# POWER.net
KiCad netlist of a schematic drawn in Altium Designer
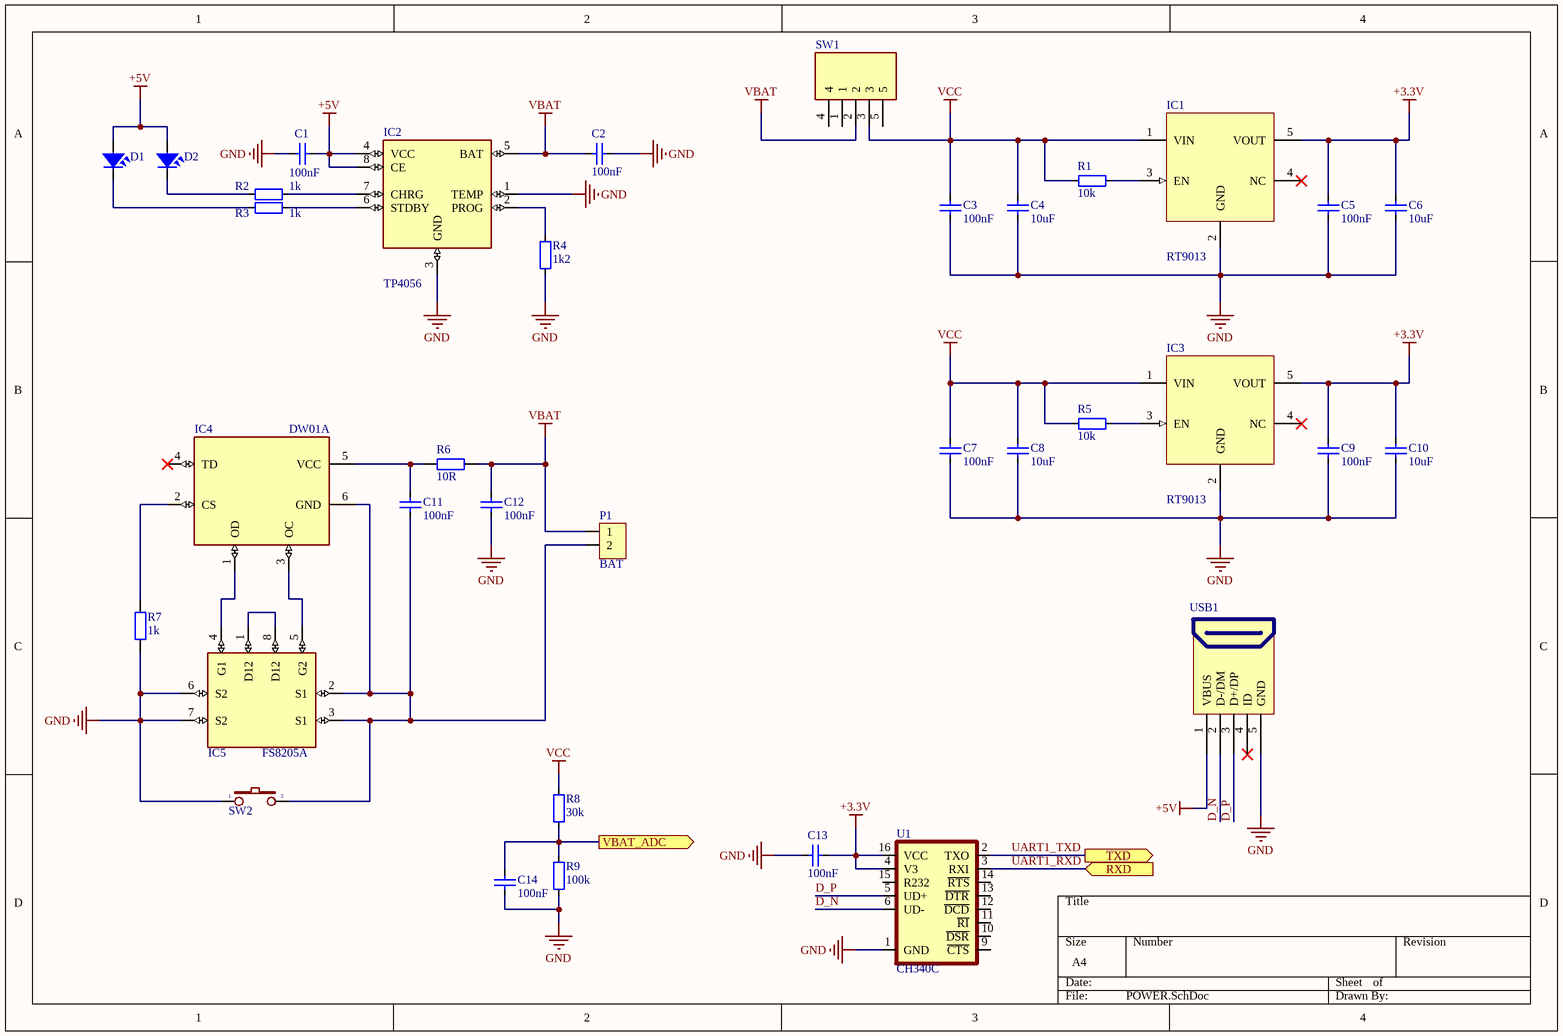
[diagram p0: POWER.SchDoc]

(export (version "E")
  (design (tool "Eeschema 10.0.6"))
  (components
    (comp (ref "C1")
      (value "100nF")
      (footprint "CAP_0603")
      (description "Capacitor")
      (fields (field (name "PUBLISHER") "Altium Limited"))
      (libsource (lib "My Library") (part "CapSMD"))
    )
    (comp (ref "C2")
      (value "100nF")
      (footprint "CAP_0603")
      (description "Capacitor")
      (fields (field (name "PUBLISHER") "Altium Limited"))
      (libsource (lib "My Library") (part "CapSMD"))
    )
    (comp (ref "C3")
      (value "100nF")
      (footprint "CAP_0603")
      (description "Capacitor")
      (fields (field (name "PUBLISHER") "Altium Limited"))
      (libsource (lib "My Library") (part "CapSMD"))
    )
    (comp (ref "C4")
      (value "10uF")
      (footprint "CAP_0603")
      (description "Capacitor")
      (fields (field (name "PUBLISHER") "Altium Limited"))
      (libsource (lib "My Library") (part "CapSMD"))
    )
    (comp (ref "C5")
      (value "100nF")
      (footprint "CAP_0603")
      (description "Capacitor")
      (fields (field (name "PUBLISHER") "Altium Limited"))
      (libsource (lib "My Library") (part "CapSMD"))
    )
    (comp (ref "C6")
      (value "10uF")
      (footprint "CAP_0603")
      (description "Capacitor")
      (fields (field (name "PUBLISHER") "Altium Limited"))
      (libsource (lib "My Library") (part "CapSMD"))
    )
    (comp (ref "C7")
      (value "100nF")
      (footprint "CAP_0603")
      (description "Capacitor")
      (fields (field (name "PUBLISHER") "Altium Limited"))
      (libsource (lib "My Library") (part "CapSMD"))
    )
    (comp (ref "C8")
      (value "10uF")
      (footprint "CAP_0603")
      (description "Capacitor")
      (fields (field (name "PUBLISHER") "Altium Limited"))
      (libsource (lib "My Library") (part "CapSMD"))
    )
    (comp (ref "C9")
      (value "100nF")
      (footprint "CAP_0603")
      (description "Capacitor")
      (fields (field (name "PUBLISHER") "Altium Limited"))
      (libsource (lib "My Library") (part "CapSMD"))
    )
    (comp (ref "C10")
      (value "10uF")
      (footprint "CAP_0603")
      (description "Capacitor")
      (fields (field (name "PUBLISHER") "Altium Limited"))
      (libsource (lib "My Library") (part "CapSMD"))
    )
    (comp (ref "C11")
      (value "100nF")
      (footprint "CAP_0603")
      (description "Capacitor")
      (fields (field (name "PUBLISHER") "Altium Limited"))
      (libsource (lib "My Library") (part "CapSMD"))
    )
    (comp (ref "C12")
      (value "100nF")
      (footprint "CAP_0603")
      (description "Capacitor")
      (fields (field (name "PUBLISHER") "Altium Limited"))
      (libsource (lib "My Library") (part "CapSMD"))
    )
    (comp (ref "C13")
      (value "100nF")
      (footprint "CAP_0603")
      (description "Capacitor")
      (fields (field (name "PUBLISHER") "Altium Limited"))
      (libsource (lib "My Library") (part "CapSMD"))
    )
    (comp (ref "C14")
      (value "100nF")
      (footprint "CAP_0603")
      (description "Capacitor")
      (fields (field (name "PUBLISHER") "Altium Limited"))
      (libsource (lib "My Library") (part "CapSMD"))
    )
    (comp (ref "D1")
      (value "BLUE")
      (footprint "LED-0603-Green")
      (description "LED Single colour Green and Red")
      (libsource (lib "My Library") (part "LED"))
    )
    (comp (ref "D2")
      (value "BLUE")
      (footprint "LED-0603-Green")
      (description "LED Single colour Green and Red")
      (libsource (lib "My Library") (part "LED"))
    )
    (comp (ref "IC1")
      (value "RT9013")
      (footprint "SOT23-5")
      (description "RT9013-33GB IC REG LINEAR 3.3V 500mA SOT23-5")
      (libsource (lib "My Library") (part "RT9013"))
    )
    (comp (ref "IC2")
      (value "TP4056")
      (footprint "TP4056")
      (description "Complete single cell Li-Ion battery with a constant current / constant voltage linear charger")
      (libsource (lib "My Library") (part "TP4056"))
    )
    (comp (ref "IC3")
      (value "RT9013")
      (footprint "SOT23-5")
      (description "RT9013-33GB IC REG LINEAR 3.3V 500mA SOT23-5")
      (libsource (lib "My Library") (part "RT9013"))
    )
    (comp (ref "IC4")
      (value "DW01A")
      (footprint "SOT23-6")
      (description "One Cell Lithium-ion/Polymer Battery Protection IC")
      (libsource (lib "My Library") (part "DW01A"))
    )
    (comp (ref "IC5") (value "FS8205A") (footprint "FS8205A") (libsource (lib "My Library") (part "FS8205A")))
    (comp (ref "P1")
      (value "BAT")
      (footprint "HEAD2P-1.25")
      (description "Header IDC, 2 x 1 Pin Vertical 2.54mm Pitch (Non-Boxed, Male)")
      (fields
        (field (name "MANUFACTURER") "Würth Elektronik eiSos GmbH")
        (field (name "PARTNO") "613002143121")
        (field (name "CREATED BY") "Karrer Zheng")
      )
      (libsource (lib "My Library") (part "Header2"))
    )
    (comp (ref "R1")
      (value "10k")
      (footprint "RES-SMD-0603")
      (description "Resistor")
      (fields
        (field (name "MANUFACTURER") "Generic Components")
        (field (name "PUBLISHER") "Altium Hobart Technology Centre")
      )
      (libsource (lib "My Library") (part "Resistor - SMD"))
    )
    (comp (ref "R2")
      (value "1k")
      (footprint "RES-SMD-0603")
      (description "Resistor")
      (fields
        (field (name "MANUFACTURER") "Generic Components")
        (field (name "PUBLISHER") "Altium Hobart Technology Centre")
      )
      (libsource (lib "My Library") (part "Resistor - SMD"))
    )
    (comp (ref "R3")
      (value "1k")
      (footprint "RES-SMD-0603")
      (description "Resistor")
      (fields
        (field (name "MANUFACTURER") "Generic Components")
        (field (name "PUBLISHER") "Altium Hobart Technology Centre")
      )
      (libsource (lib "My Library") (part "Resistor - SMD"))
    )
    (comp (ref "R4")
      (value "1k2")
      (footprint "RES-SMD-0603")
      (description "Resistor")
      (fields
        (field (name "MANUFACTURER") "Generic Components")
        (field (name "PUBLISHER") "Altium Hobart Technology Centre")
      )
      (libsource (lib "My Library") (part "Resistor - SMD"))
    )
    (comp (ref "R5")
      (value "10k")
      (footprint "RES-SMD-0603")
      (description "Resistor")
      (fields
        (field (name "MANUFACTURER") "Generic Components")
        (field (name "PUBLISHER") "Altium Hobart Technology Centre")
      )
      (libsource (lib "My Library") (part "Resistor - SMD"))
    )
    (comp (ref "R6")
      (value "10R")
      (footprint "RES-SMD-0603")
      (description "Resistor SMD")
      (fields
        (field (name "MANUFACTURER") "Generic Components")
        (field (name "PUBLISHER") "Altium Hobart Technology Centre")
      )
      (libsource (lib "") (part "Resistor - SMD_1"))
    )
    (comp (ref "R7")
      (value "1k")
      (footprint "RES-SMD-0603")
      (description "Resistor SMD")
      (fields
        (field (name "MANUFACTURER") "Generic Components")
        (field (name "PUBLISHER") "Altium Hobart Technology Centre")
      )
      (libsource (lib "") (part "Resistor - SMD_1"))
    )
    (comp (ref "R8")
      (value "30k")
      (footprint "RES-SMD-0603")
      (description "Resistor")
      (fields
        (field (name "MANUFACTURER") "Generic Components")
        (field (name "PUBLISHER") "Altium Hobart Technology Centre")
      )
      (libsource (lib "My Library") (part "Resistor - SMD"))
    )
    (comp (ref "R9")
      (value "100k")
      (footprint "RES-SMD-0603")
      (description "Resistor")
      (fields
        (field (name "MANUFACTURER") "Generic Components")
        (field (name "PUBLISHER") "Altium Hobart Technology Centre")
      )
      (libsource (lib "My Library") (part "Resistor - SMD"))
    )
    (comp (ref "SW1")
      (value "Cong tac gat")
      (footprint "CONG-TAC-GAT")
      (libsource (lib "Dung Library") (part "Cong tac gat"))
    )
    (comp (ref "SW2") (value "SW") (footprint "SW") (libsource (lib "Dung Library") (part "SW")))
    (comp (ref "U1")
      (value "CH340C")
      (footprint "SO16")
      (description "USB to serial chip CH340")
      (fields (field (name "MF") "WCH"))
      (libsource (lib "My Library") (part "CH340C"))
    )
    (comp (ref "USB1")
      (value "USB Micro 5p DIP")
      (footprint "USB Micro 5p DIP")
      (description "USB Type B")
      (libsource (lib "Altium_Lib_by_KhueNguyenCreator") (part "USB Micro 5p DIP"))
    )
  )
  (nets
    (net (code "1") (name "+3.3V") (class "Default")
      (node (ref "C10") (pin "1") (pinfunction "1_1") (pintype "passive"))
      (node (ref "C13") (pin "1") (pinfunction "1_1") (pintype "passive"))
      (node (ref "C5") (pin "1") (pinfunction "1_1") (pintype "passive"))
      (node (ref "C6") (pin "1") (pinfunction "1_1") (pintype "passive"))
      (node (ref "C9") (pin "1") (pinfunction "1_1") (pintype "passive"))
      (node (ref "IC1") (pin "5") (pinfunction "VOUT_5") (pintype "power_in"))
      (node (ref "IC3") (pin "5") (pinfunction "VOUT_5") (pintype "power_in"))
      (node (ref "U1") (pin "16") (pinfunction "VCC_16") (pintype "bidirectional"))
      (node (ref "U1") (pin "4") (pinfunction "V3_4") (pintype "bidirectional"))
    )
    (net (code "2") (name "+5V") (class "Default")
      (node (ref "C1") (pin "1") (pinfunction "1_1") (pintype "passive"))
      (node (ref "D1") (pin "1") (pinfunction "1_1") (pintype "passive"))
      (node (ref "D2") (pin "1") (pinfunction "1_1") (pintype "passive"))
      (node (ref "IC2") (pin "4") (pinfunction "VCC_4") (pintype "bidirectional"))
      (node (ref "IC2") (pin "8") (pinfunction "CE_8") (pintype "bidirectional"))
      (node (ref "USB1") (pin "1") (pinfunction "VBUS_1") (pintype "passive"))
    )
    (net (code "3") (name "/D_N") (class "Default")
      (node (ref "U1") (pin "6") (pinfunction "UD-_6") (pintype "bidirectional"))
      (node (ref "USB1") (pin "2") (pinfunction "D-/DM_2") (pintype "passive"))
    )
    (net (code "4") (name "/D_P") (class "Default")
      (node (ref "U1") (pin "5") (pinfunction "UD+_5") (pintype "bidirectional"))
      (node (ref "USB1") (pin "3") (pinfunction "D+/DP_3") (pintype "passive"))
    )
    (net (code "5") (name "/UART1_RXD") (class "Default")
      (node (ref "U1") (pin "3") (pinfunction "RXI_3") (pintype "bidirectional"))
    )
    (net (code "6") (name "/UART1_TXD") (class "Default")
      (node (ref "U1") (pin "2") (pinfunction "TXO_2") (pintype "bidirectional"))
    )
    (net (code "7") (name "/VBAT_ADC") (class "Default")
      (node (ref "C14") (pin "2") (pinfunction "2_2") (pintype "passive"))
      (node (ref "R8") (pin "2") (pinfunction "2_2") (pintype "passive"))
      (node (ref "R9") (pin "1") (pinfunction "1_1") (pintype "passive"))
    )
    (net (code "8") (name "GND") (class "Default")
      (node (ref "C1") (pin "2") (pinfunction "2_2") (pintype "passive"))
      (node (ref "C10") (pin "2") (pinfunction "2_2") (pintype "passive"))
      (node (ref "C12") (pin "1") (pinfunction "1_1") (pintype "passive"))
      (node (ref "C13") (pin "2") (pinfunction "2_2") (pintype "passive"))
      (node (ref "C14") (pin "1") (pinfunction "1_1") (pintype "passive"))
      (node (ref "C2") (pin "1") (pinfunction "1_1") (pintype "passive"))
      (node (ref "C3") (pin "2") (pinfunction "2_2") (pintype "passive"))
      (node (ref "C4") (pin "2") (pinfunction "2_2") (pintype "passive"))
      (node (ref "C5") (pin "2") (pinfunction "2_2") (pintype "passive"))
      (node (ref "C6") (pin "2") (pinfunction "2_2") (pintype "passive"))
      (node (ref "C7") (pin "2") (pinfunction "2_2") (pintype "passive"))
      (node (ref "C8") (pin "2") (pinfunction "2_2") (pintype "passive"))
      (node (ref "C9") (pin "2") (pinfunction "2_2") (pintype "passive"))
      (node (ref "IC1") (pin "2") (pinfunction "GND_2") (pintype "power_in"))
      (node (ref "IC2") (pin "1") (pinfunction "TEMP_1") (pintype "bidirectional"))
      (node (ref "IC2") (pin "3") (pinfunction "GND_3") (pintype "bidirectional"))
      (node (ref "IC3") (pin "2") (pinfunction "GND_2") (pintype "power_in"))
      (node (ref "IC5") (pin "6") (pinfunction "S2_6") (pintype "bidirectional"))
      (node (ref "IC5") (pin "7") (pinfunction "S2_7") (pintype "bidirectional"))
      (node (ref "R4") (pin "1") (pinfunction "1_1") (pintype "passive"))
      (node (ref "R7") (pin "2") (pinfunction "2_2") (pintype "passive"))
      (node (ref "R9") (pin "2") (pinfunction "2_2") (pintype "passive"))
      (node (ref "SW2") (pin "1") (pinfunction "1_1") (pintype "passive"))
      (node (ref "U1") (pin "1") (pinfunction "GND_1") (pintype "bidirectional"))
      (node (ref "USB1") (pin "5") (pinfunction "GND_5") (pintype "passive"))
    )
    (net (code "9") (name "Net-(D1-Pad2)") (class "Default")
      (node (ref "D1") (pin "2") (pinfunction "2_2") (pintype "passive"))
      (node (ref "R3") (pin "2") (pinfunction "2_2") (pintype "passive"))
    )
    (net (code "10") (name "Net-(D2-Pad2)") (class "Default")
      (node (ref "D2") (pin "2") (pinfunction "2_2") (pintype "passive"))
      (node (ref "R2") (pin "2") (pinfunction "2_2") (pintype "passive"))
    )
    (net (code "11") (name "Net-(IC1-EN)") (class "Default")
      (node (ref "IC1") (pin "3") (pinfunction "EN_3") (pintype "input"))
      (node (ref "R1") (pin "1") (pinfunction "1_1") (pintype "passive"))
    )
    (net (code "12") (name "Net-(IC2-CHRG)") (class "Default")
      (node (ref "IC2") (pin "7") (pinfunction "CHRG_7") (pintype "bidirectional"))
      (node (ref "R2") (pin "1") (pinfunction "1_1") (pintype "passive"))
    )
    (net (code "13") (name "Net-(IC2-PROG)") (class "Default")
      (node (ref "IC2") (pin "2") (pinfunction "PROG_2") (pintype "bidirectional"))
      (node (ref "R4") (pin "2") (pinfunction "2_2") (pintype "passive"))
    )
    (net (code "14") (name "Net-(IC2-STDBY)") (class "Default")
      (node (ref "IC2") (pin "6") (pinfunction "STDBY_6") (pintype "bidirectional"))
      (node (ref "R3") (pin "1") (pinfunction "1_1") (pintype "passive"))
    )
    (net (code "15") (name "Net-(IC3-EN)") (class "Default")
      (node (ref "IC3") (pin "3") (pinfunction "EN_3") (pintype "input"))
      (node (ref "R5") (pin "1") (pinfunction "1_1") (pintype "passive"))
    )
    (net (code "16") (name "Net-(IC4-CS)") (class "Default")
      (node (ref "IC4") (pin "2") (pinfunction "CS_2") (pintype "bidirectional"))
      (node (ref "R7") (pin "1") (pinfunction "1_1") (pintype "passive"))
    )
    (net (code "17") (name "Net-(IC4-GND)") (class "Default")
      (node (ref "C11") (pin "1") (pinfunction "1_1") (pintype "passive"))
      (node (ref "IC4") (pin "6") (pinfunction "GND_6") (pintype "power_in"))
      (node (ref "IC5") (pin "2") (pinfunction "S1_2") (pintype "bidirectional"))
      (node (ref "IC5") (pin "3") (pinfunction "S1_3") (pintype "bidirectional"))
      (node (ref "P1") (pin "2") (pinfunction "2_2") (pintype "passive"))
      (node (ref "SW2") (pin "2") (pinfunction "2_2") (pintype "passive"))
    )
    (net (code "18") (name "Net-(IC4-OC)") (class "Default")
      (node (ref "IC4") (pin "3") (pinfunction "OC_3") (pintype "bidirectional"))
      (node (ref "IC5") (pin "5") (pinfunction "G2_5") (pintype "bidirectional"))
    )
    (net (code "19") (name "Net-(IC4-OD)") (class "Default")
      (node (ref "IC4") (pin "1") (pinfunction "OD_1") (pintype "bidirectional"))
      (node (ref "IC5") (pin "4") (pinfunction "G1_4") (pintype "bidirectional"))
    )
    (net (code "20") (name "Net-(IC4-VCC)") (class "Default")
      (node (ref "C11") (pin "2") (pinfunction "2_2") (pintype "passive"))
      (node (ref "IC4") (pin "5") (pinfunction "VCC_5") (pintype "power_in"))
      (node (ref "R6") (pin "1") (pinfunction "1_1") (pintype "passive"))
    )
    (net (code "21") (name "Net-(IC5-D12-Pad1)") (class "Default")
      (node (ref "IC5") (pin "1") (pinfunction "D12_1") (pintype "bidirectional"))
      (node (ref "IC5") (pin "8") (pinfunction "D12_8") (pintype "bidirectional"))
    )
    (net (code "22") (name "VBAT") (class "Default")
      (node (ref "C12") (pin "2") (pinfunction "2_2") (pintype "passive"))
      (node (ref "C2") (pin "2") (pinfunction "2_2") (pintype "passive"))
      (node (ref "IC2") (pin "5") (pinfunction "BAT_5") (pintype "bidirectional"))
      (node (ref "P1") (pin "1") (pinfunction "1_1") (pintype "passive"))
      (node (ref "R6") (pin "2") (pinfunction "2_2") (pintype "passive"))
      (node (ref "SW1") (pin "2") (pinfunction "2_2") (pintype "passive"))
    )
    (net (code "23") (name "VCC") (class "Default")
      (node (ref "C3") (pin "1") (pinfunction "1_1") (pintype "passive"))
      (node (ref "C4") (pin "1") (pinfunction "1_1") (pintype "passive"))
      (node (ref "C7") (pin "1") (pinfunction "1_1") (pintype "passive"))
      (node (ref "C8") (pin "1") (pinfunction "1_1") (pintype "passive"))
      (node (ref "IC1") (pin "1") (pinfunction "VIN_1") (pintype "power_in"))
      (node (ref "IC3") (pin "1") (pinfunction "VIN_1") (pintype "power_in"))
      (node (ref "R1") (pin "2") (pinfunction "2_2") (pintype "passive"))
      (node (ref "R5") (pin "2") (pinfunction "2_2") (pintype "passive"))
      (node (ref "R8") (pin "1") (pinfunction "1_1") (pintype "passive"))
      (node (ref "SW1") (pin "3") (pinfunction "3_3") (pintype "passive"))
    )
    (net (code "24") (name "unconnected-(IC1-NC-Pad4)") (class "Default")
      (node (ref "IC1") (pin "4") (pinfunction "NC_4") (pintype "passive+no_connect"))
    )
    (net (code "25") (name "unconnected-(IC3-NC-Pad4)") (class "Default")
      (node (ref "IC3") (pin "4") (pinfunction "NC_4") (pintype "passive+no_connect"))
    )
    (net (code "26") (name "unconnected-(IC4-TD-Pad4)") (class "Default")
      (node (ref "IC4") (pin "4") (pinfunction "TD_4") (pintype "bidirectional+no_connect"))
    )
    (net (code "27") (name "unconnected-(SW1-Pad1)") (class "Default")
      (node (ref "SW1") (pin "1") (pinfunction "1_1") (pintype "passive"))
    )
    (net (code "28") (name "unconnected-(SW1-Pad4)") (class "Default")
      (node (ref "SW1") (pin "4") (pinfunction "4_4") (pintype "passive"))
    )
    (net (code "29") (name "unconnected-(SW1-Pad5)") (class "Default")
      (node (ref "SW1") (pin "5") (pinfunction "5_5") (pintype "passive"))
    )
    (net (code "30") (name "unconnected-(U1-R232-Pad15)") (class "Default")
      (node (ref "U1") (pin "15") (pinfunction "R232_15") (pintype "bidirectional"))
    )
    (net (code "31") (name "unconnected-(U1-~{CTS}-Pad9)") (class "Default")
      (node (ref "U1") (pin "9") (pinfunction "~{CTS}_9") (pintype "bidirectional"))
    )
    (net (code "32") (name "unconnected-(U1-~{DCD}-Pad12)") (class "Default")
      (node (ref "U1") (pin "12") (pinfunction "~{DCD}_12") (pintype "bidirectional"))
    )
    (net (code "33") (name "unconnected-(U1-~{DSR}-Pad10)") (class "Default")
      (node (ref "U1") (pin "10") (pinfunction "~{DSR}_10") (pintype "bidirectional"))
    )
    (net (code "34") (name "unconnected-(U1-~{DTR}-Pad13)") (class "Default")
      (node (ref "U1") (pin "13") (pinfunction "~{DTR}_13") (pintype "bidirectional"))
    )
    (net (code "35") (name "unconnected-(U1-~{RI}-Pad11)") (class "Default")
      (node (ref "U1") (pin "11") (pinfunction "~{RI}_11") (pintype "bidirectional"))
    )
    (net (code "36") (name "unconnected-(U1-~{RTS}-Pad14)") (class "Default")
      (node (ref "U1") (pin "14") (pinfunction "~{RTS}_14") (pintype "bidirectional"))
    )
    (net (code "37") (name "unconnected-(USB1-ID-Pad4)") (class "Default")
      (node (ref "USB1") (pin "4") (pinfunction "ID_4") (pintype "passive+no_connect"))
    )
  )
)
